# BACKPMAN20_PwrSw.net
KiCad netlist of a schematic drawn in Altium Designer
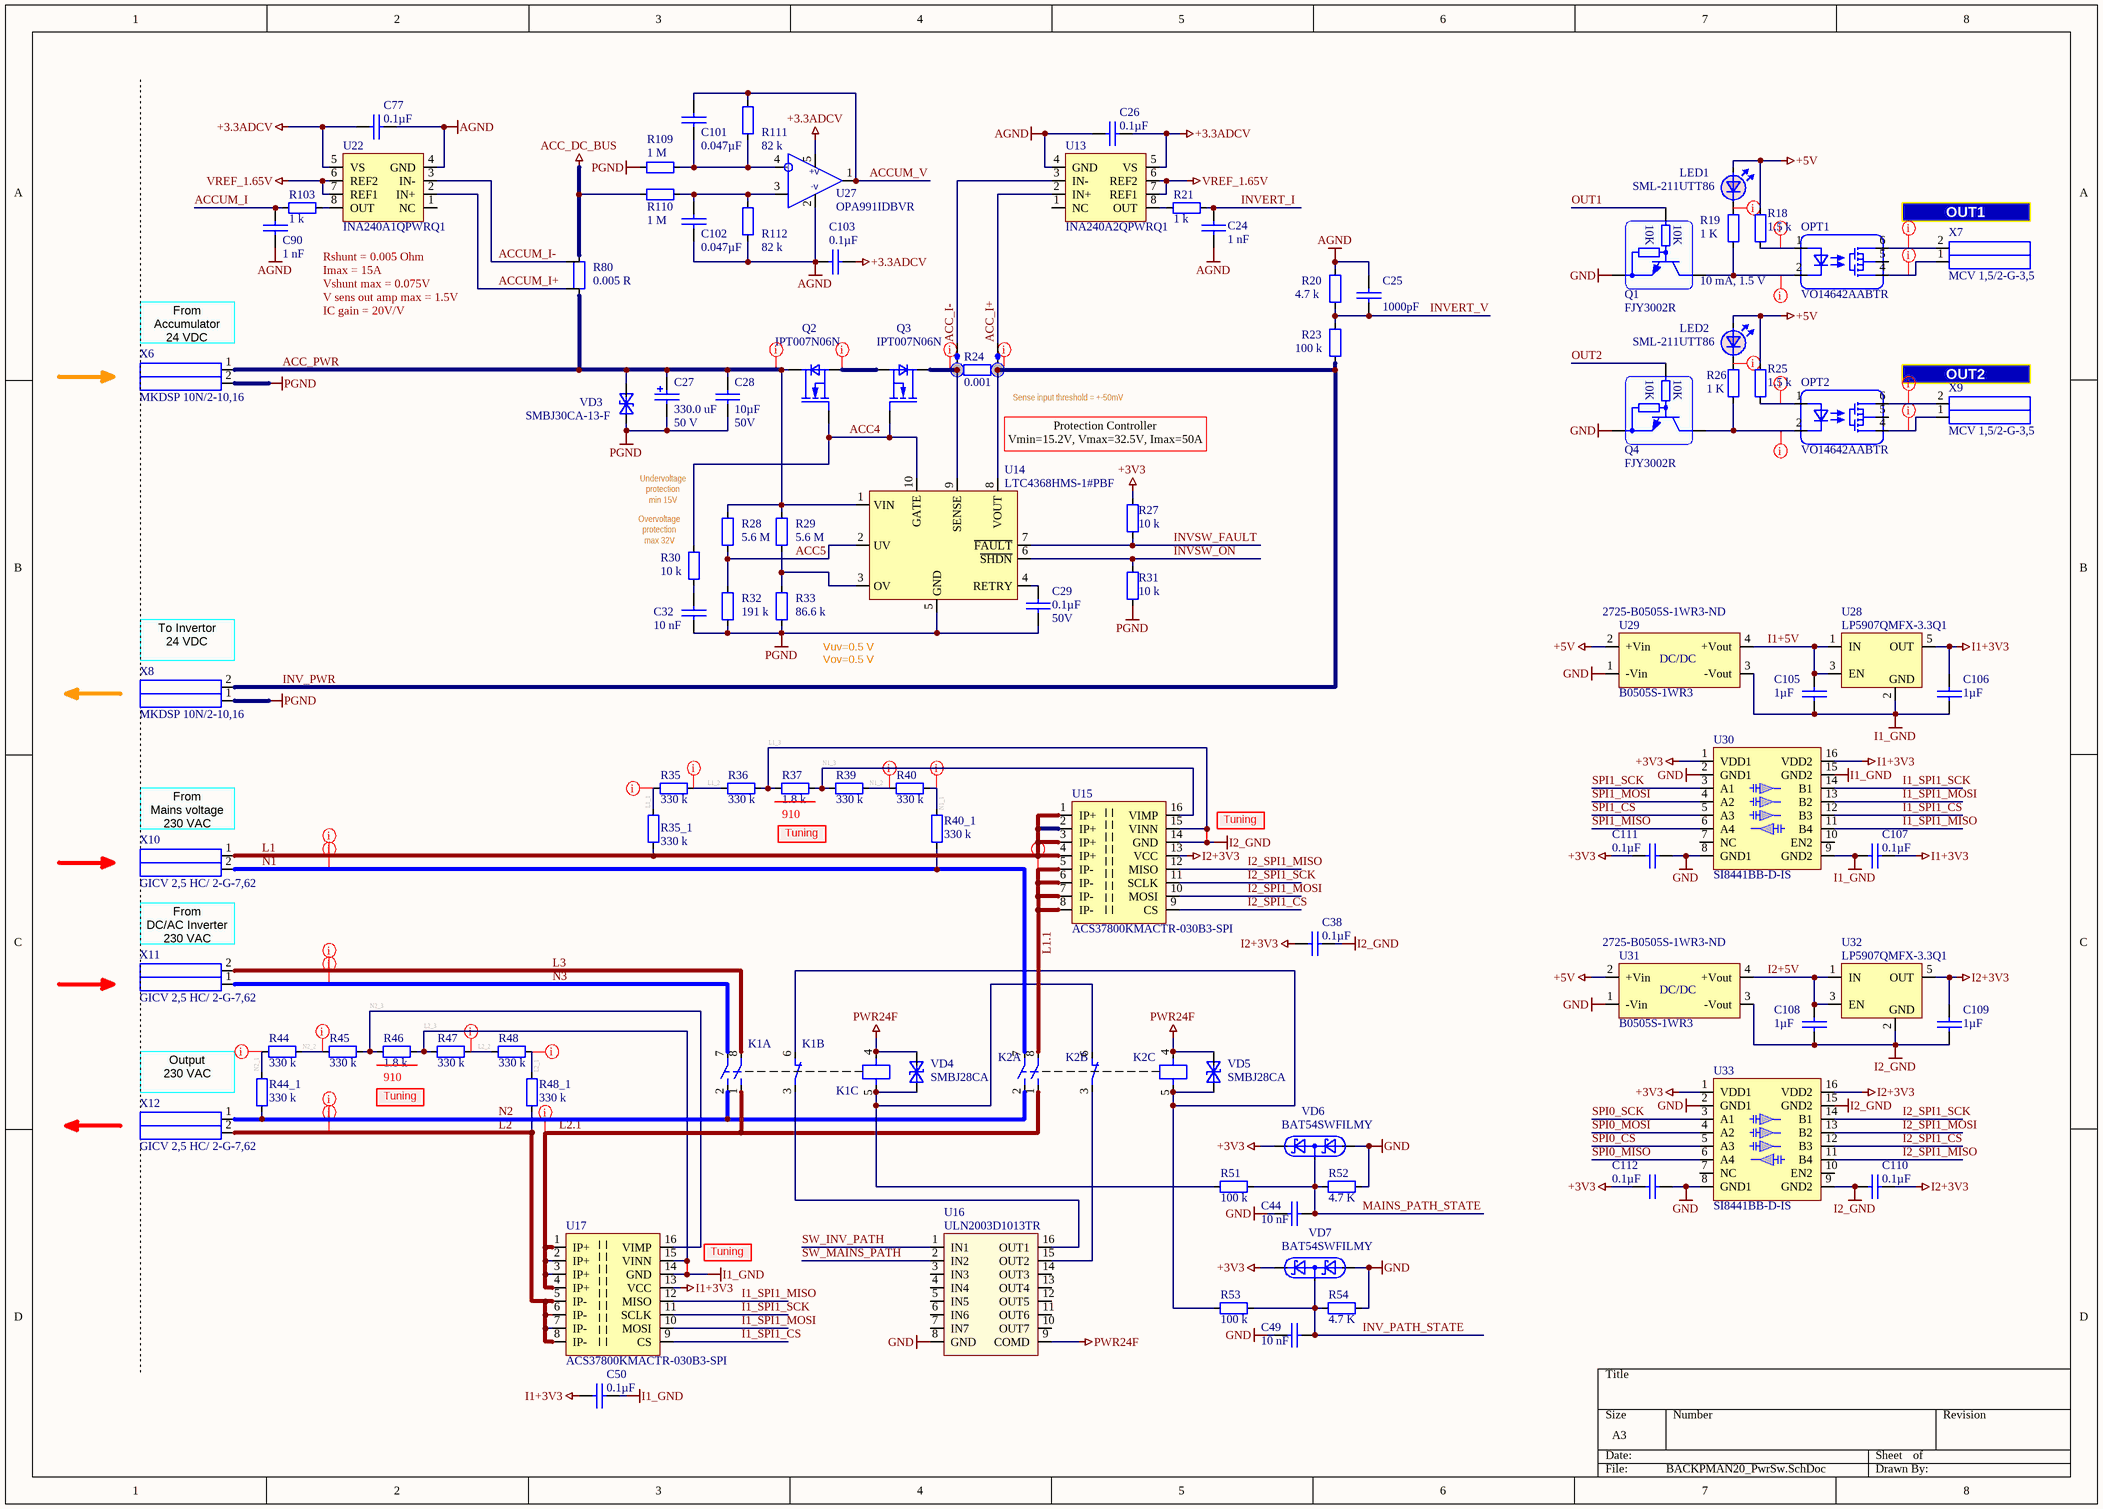
[diagram p0: BACKPMAN20_PwrSw.SchDoc]

(export (version "E")
  (design (tool "Eeschema 10.0.6"))
  (components
    (comp (ref "B1")
      (value "Net tie 0.3mm")
      (footprint "Net tee 0.3 mm")
      (libsource (lib "ea_Mechanical") (part "Net tie 0.3mm"))
    )
    (comp (ref "B2")
      (value "Net tie 0.3mm")
      (footprint "Net tee 0.3 mm")
      (libsource (lib "ea_Mechanical") (part "Net tie 0.3mm"))
    )
    (comp (ref "C24")
      (value "1 nF")
      (footprint "0603 CAP")
      (description "1000pF, ±5%, 50V, X7R, 0603 (1608 Metric), -55°C ~ 125°C, -, General Purpose")
      (fields (field (name "PART NUMBER") "CC0603JRX7R9BB102") (field (name "MANUFACTURER") "Yageo"))
      (libsource (lib "ea_PassivComps") (part "Capacitor"))
    )
    (comp (ref "C25")
      (value "1000pF")
      (footprint "0603 CAP")
      (description "1000pF, ±10%, 16V, X7R, 0603 (1608 Metric), -55°C ~ 125°C, -, General Purpose")
      (fields
        (field (name "PART NUMBER") "885012206034")
        (field (name "MANUFACTURER") "Wurth Electronics Inc.")
      )
      (libsource (lib "ea_PassivComps") (part "Capacitor"))
    )
    (comp (ref "C26")
      (value "0.1µF")
      (footprint "0603 CAP")
      (description "0.1µF, ±10%, 50V, X8L, 0603 (1608 Metric), -55°C ~ 150°C, -, Automotive")
      (fields
        (field (name "PART NUMBER") "GCM188L81H104KA57D")
        (field (name "MANUFACTURER") "Murata Electronics North America")
      )
      (libsource (lib "ea_PassivComps") (part "Capacitor"))
    )
    (comp (ref "C27")
      (value "330.0 uF")
      (footprint "UUD1V331MNL1GS")
      (description "330 uF, 50V, 120 mOhm @ 100kHz, 585 mA, 10x10, -50...+105 C")
      (fields
        (field (name "MANUFACTURER") "Panasonic Electronic Components")
        (field (name "VOLTAGE") "50 V")
        (field (name "TOLERANCE") "±20%")
      )
      (libsource (lib "ea_Capacitors") (part "EEE-FT1H331GP"))
    )
    (comp (ref "C28")
      (value "10µF")
      (footprint "1210 CAP")
      (description "10µF, ±10%, 50V, X7S, 1210 (3225 Metric), -55°C ~ 125°C, Low ESL, General Purpose")
      (fields
        (field (name "VOLTAGE - RATED") "50V")
        (field (name "PART NUMBER") "C3225X7S1H106K250AB")
        (field (name "MANUFACTURER") "TDK Corporation")
      )
      (libsource (lib "ea_PassivComps") (part "Capacitor"))
    )
    (comp (ref "C29")
      (value "0.1µF")
      (footprint "0603 CAP")
      (description "0.1µF, ±10%, 50V, X8L, 0603 (1608 Metric), -55°C ~ 150°C, -, Automotive")
      (fields
        (field (name "VOLTAGE - RATED") "50V")
        (field (name "PART NUMBER") "GCM188L81H104KA57D")
        (field (name "MANUFACTURER") "Murata Electronics North America")
      )
      (libsource (lib "ea_PassivComps") (part "Capacitor"))
    )
    (comp (ref "C32")
      (value "10 nF")
      (footprint "1608[0603]")
      (description "10 nF, 50V, 10%, X7R, 0603 SMD MLC Capacitor")
      (fields (field (name "TOLERANCE") "±10%") (field (name "MANUFACTURER") "Murata Electronics"))
      (libsource (lib "ea_Capacitors") (part "CVNF010K0603"))
    )
    (comp (ref "C38")
      (value "0.1µF")
      (footprint "0603 CAP")
      (description "0.1µF, ±10%, 16V, X7R, 0603 (1608 Metric), -55°C ~ 125°C, -, General Purpose")
      (fields
        (field (name "PART NUMBER") "CL10B104KO8NNNC")
        (field (name "MANUFACTURER") "Samsung Electro-Mechanics")
      )
      (libsource (lib "ea_PassivComps") (part "Capacitor"))
    )
    (comp (ref "C44")
      (value "10 nF")
      (footprint "1608[0603]")
      (description "10 nF, 50V, 10%, X7R, 0603 SMD MLC Capacitor")
      (fields (field (name "TOLERANCE") "±10%") (field (name "MANUFACTURER") "Murata Electronics"))
      (libsource (lib "ea_Capacitors") (part "CVNF010K0603"))
    )
    (comp (ref "C49")
      (value "10 nF")
      (footprint "1608[0603]")
      (description "10 nF, 50V, 10%, X7R, 0603 SMD MLC Capacitor")
      (fields (field (name "TOLERANCE") "±10%") (field (name "MANUFACTURER") "Murata Electronics"))
      (libsource (lib "ea_Capacitors") (part "CVNF010K0603"))
    )
    (comp (ref "C50")
      (value "0.1µF")
      (footprint "0603 CAP")
      (description "0.1µF, ±10%, 16V, X7R, 0603 (1608 Metric), -55°C ~ 125°C, -, General Purpose")
      (fields
        (field (name "PART NUMBER") "CL10B104KO8NNNC")
        (field (name "MANUFACTURER") "Samsung Electro-Mechanics")
      )
      (libsource (lib "ea_PassivComps") (part "Capacitor"))
    )
    (comp (ref "C77")
      (value "0.1µF")
      (footprint "0603 CAP")
      (description "0.1µF, ±10%, 50V, X8L, 0603 (1608 Metric), -55°C ~ 150°C, -, Automotive")
      (fields
        (field (name "PART NUMBER") "GCM188L81H104KA57D")
        (field (name "MANUFACTURER") "Murata Electronics North America")
      )
      (libsource (lib "ea_PassivComps") (part "Capacitor"))
    )
    (comp (ref "C90")
      (value "1 nF")
      (footprint "0603 CAP")
      (description "1000pF, ±5%, 50V, X7R, 0603 (1608 Metric), -55°C ~ 125°C, -, General Purpose")
      (fields (field (name "PART NUMBER") "CC0603JRX7R9BB102") (field (name "MANUFACTURER") "Yageo"))
      (libsource (lib "ea_PassivComps") (part "Capacitor"))
    )
    (comp (ref "C101")
      (value "0.047µF")
      (footprint "0603 CAP")
      (description "0.047µF, ±5%, 50V, X7R, 0603 (1608 Metric), -55°C ~ 125°C, -, General Purpose")
      (fields (field (name "PART NUMBER") "CC0603JRX7R9BB473") (field (name "MANUFACTURER") "Yageo"))
      (libsource (lib "ea_PassivComps") (part "Capacitor"))
    )
    (comp (ref "C102")
      (value "0.047µF")
      (footprint "0603 CAP")
      (description "0.047µF, ±5%, 50V, X7R, 0603 (1608 Metric), -55°C ~ 125°C, -, General Purpose")
      (fields (field (name "PART NUMBER") "CC0603JRX7R9BB473") (field (name "MANUFACTURER") "Yageo"))
      (libsource (lib "ea_PassivComps") (part "Capacitor"))
    )
    (comp (ref "C103")
      (value "0.1µF")
      (footprint "0603 CAP")
      (description "0.1µF, ±10%, 50V, X8L, 0603 (1608 Metric), -55°C ~ 150°C, -, Automotive")
      (fields
        (field (name "PART NUMBER") "GCM188L81H104KA57D")
        (field (name "MANUFACTURER") "Murata Electronics North America")
      )
      (libsource (lib "ea_PassivComps") (part "Capacitor"))
    )
    (comp (ref "C105")
      (value "1µF")
      (footprint "0603 CAP")
      (description "1µF, ±10%, 16V, X7R, 0603 (1608 Metric), -55°C ~ 125°C, -, General Purpose")
      (fields
        (field (name "PART NUMBER") "CL10B105KO8NNNC")
        (field (name "MANUFACTURER") "Samsung Electro-Mechanics")
      )
      (libsource (lib "ea_PassivComps") (part "Capacitor"))
    )
    (comp (ref "C106")
      (value "1µF")
      (footprint "0603 CAP")
      (description "1µF, ±10%, 16V, X7R, 0603 (1608 Metric), -55°C ~ 125°C, -, General Purpose")
      (fields
        (field (name "PART NUMBER") "CL10B105KO8NNNC")
        (field (name "MANUFACTURER") "Samsung Electro-Mechanics")
      )
      (libsource (lib "ea_PassivComps") (part "Capacitor"))
    )
    (comp (ref "C107")
      (value "0.1µF")
      (footprint "0603 CAP")
      (description "0.1µF, ±10%, 16V, X7R, 0603 (1608 Metric), -55°C ~ 125°C, -, General Purpose")
      (fields
        (field (name "PART NUMBER") "CL10B104KO8NNNC")
        (field (name "MANUFACTURER") "Samsung Electro-Mechanics")
      )
      (libsource (lib "ea_PassivComps") (part "Capacitor"))
    )
    (comp (ref "C108")
      (value "1µF")
      (footprint "0603 CAP")
      (description "1µF, ±10%, 16V, X7R, 0603 (1608 Metric), -55°C ~ 125°C, -, General Purpose")
      (fields
        (field (name "PART NUMBER") "CL10B105KO8NNNC")
        (field (name "MANUFACTURER") "Samsung Electro-Mechanics")
      )
      (libsource (lib "ea_PassivComps") (part "Capacitor"))
    )
    (comp (ref "C109")
      (value "1µF")
      (footprint "0603 CAP")
      (description "1µF, ±10%, 16V, X7R, 0603 (1608 Metric), -55°C ~ 125°C, -, General Purpose")
      (fields
        (field (name "PART NUMBER") "CL10B105KO8NNNC")
        (field (name "MANUFACTURER") "Samsung Electro-Mechanics")
      )
      (libsource (lib "ea_PassivComps") (part "Capacitor"))
    )
    (comp (ref "C110")
      (value "0.1µF")
      (footprint "0603 CAP")
      (description "0.1µF, ±10%, 16V, X7R, 0603 (1608 Metric), -55°C ~ 125°C, -, General Purpose")
      (fields
        (field (name "PART NUMBER") "CL10B104KO8NNNC")
        (field (name "MANUFACTURER") "Samsung Electro-Mechanics")
      )
      (libsource (lib "ea_PassivComps") (part "Capacitor"))
    )
    (comp (ref "C111")
      (value "0.1µF")
      (footprint "0603 CAP")
      (description "0.1µF, ±10%, 16V, X7R, 0603 (1608 Metric), -55°C ~ 125°C, -, General Purpose")
      (fields
        (field (name "PART NUMBER") "CL10B104KO8NNNC")
        (field (name "MANUFACTURER") "Samsung Electro-Mechanics")
      )
      (libsource (lib "ea_PassivComps") (part "Capacitor"))
    )
    (comp (ref "C112")
      (value "0.1µF")
      (footprint "0603 CAP")
      (description "0.1µF, ±10%, 16V, X7R, 0603 (1608 Metric), -55°C ~ 125°C, -, General Purpose")
      (fields
        (field (name "PART NUMBER") "CL10B104KO8NNNC")
        (field (name "MANUFACTURER") "Samsung Electro-Mechanics")
      )
      (libsource (lib "ea_PassivComps") (part "Capacitor"))
    )
    (comp (ref "K1")
      (value "AHES4292")
      (footprint "AHES4292")
      (fields (field (name "PARTNUM") "255-5914-ND") (field (name "MANUFACTURER") "Panasonic Electric Works"))
      (libsource (lib "ea_Relay") (part "AHES4292"))
    )
    (comp (ref "K2")
      (value "AHES4292")
      (footprint "AHES4292")
      (fields (field (name "PARTNUM") "255-5914-ND") (field (name "MANUFACTURER") "Panasonic Electric Works"))
      (libsource (lib "ea_Relay") (part "AHES4292"))
    )
    (comp (ref "LED1")
      (value "SML-211UTT86")
      (footprint "0805 LED")
      (description "0805 red LED, hibright, 2 mA, 1.8V, 130°")
      (fields (field (name "MANUFACTURER") "Rohm") (field (name "PARTNUM") "511-1292-1-ND"))
      (libsource (lib "ea_Indicators") (part "SML-211UTT86"))
    )
    (comp (ref "LED2")
      (value "SML-211UTT86")
      (footprint "0805 LED")
      (description "0805 red LED, hibright, 2 mA, 1.8V, 130°")
      (fields (field (name "MANUFACTURER") "Rohm") (field (name "PARTNUM") "511-1292-1-ND"))
      (libsource (lib "ea_Indicators") (part "SML-211UTT86"))
    )
    (comp (ref "OPT1")
      (value "VO14642AABTR")
      (footprint "DIP-6 SMD")
      (description "Opto relay, SPST-NO, AC DC, 250 mOhm, 2A, 0-60V, 6-SMD, -55..50C")
      (fields
        (field (name "MANUFACTURER") "Vishay Semiconductor Opto Division")
        (field (name "PARTNUM") "VO14642AABCT-ND")
      )
      (libsource (lib "ea_Opto") (part "VO14642AABTR"))
    )
    (comp (ref "OPT2")
      (value "VO14642AABTR")
      (footprint "DIP-6 SMD")
      (description "Opto relay, SPST-NO, AC DC, 250 mOhm, 2A, 0-60V, 6-SMD, -55..50C")
      (fields
        (field (name "MANUFACTURER") "Vishay Semiconductor Opto Division")
        (field (name "PARTNUM") "VO14642AABCT-ND")
      )
      (libsource (lib "ea_Opto") (part "VO14642AABTR"))
    )
    (comp (ref "Q1")
      (value "FJY3002R")
      (footprint "SOT-523F")
      (description "NPN 50V 100MA SOT-523F")
      (fields
        (field (name "MANUFACTURER") "Fairchild Semiconductor")
        (field (name "PARTNUM") "FJY3002RCT-ND")
      )
      (libsource (lib "ea_Transistors") (part "FJY3002R"))
    )
    (comp (ref "Q2")
      (value "IPT007N06N")
      (footprint "PG-HSOF-8-1 (8-PowerSFN) Infineon")
      (description "MOSFET N CH 60V 300A, 0.75 mOhm @ 150A 10V, 287nC @ 10V, PG-HSOF-8-1, -55°C ~ 175°C")
      (fields
        (field (name "MANUFACTURER") "Infineon Technologies")
        (field (name "PARTNUM") "IPT007N06NATMA1CT-ND")
      )
      (libsource (lib "ea_MOSFET_&_drivers") (part "IPT007N06NATMA1"))
    )
    (comp (ref "Q3")
      (value "IPT007N06N")
      (footprint "PG-HSOF-8-1 (8-PowerSFN) Infineon")
      (description "MOSFET N CH 60V 300A, 0.75 mOhm @ 150A 10V, 287nC @ 10V, PG-HSOF-8-1, -55°C ~ 175°C")
      (fields
        (field (name "MANUFACTURER") "Infineon Technologies")
        (field (name "PARTNUM") "IPT007N06NATMA1CT-ND")
      )
      (libsource (lib "ea_MOSFET_&_drivers") (part "IPT007N06NATMA1"))
    )
    (comp (ref "Q4")
      (value "FJY3002R")
      (footprint "SOT-523F")
      (description "NPN 50V 100MA SOT-523F")
      (fields
        (field (name "MANUFACTURER") "Fairchild Semiconductor")
        (field (name "PARTNUM") "FJY3002RCT-ND")
      )
      (libsource (lib "ea_Transistors") (part "FJY3002R"))
    )
    (comp (ref "R18")
      (value "1.5 k")
      (footprint "0603")
      (fields
        (field (name "MANUFACTURER") "Stackpole Electronics Inc.")
        (field (name "TOLERANCE") "±1%")
        (field (name "VOLTAGE") "75V")
      )
      (libsource (lib "") (part "Resistor_2"))
    )
    (comp (ref "R19")
      (value "1 K")
      (footprint "0603")
      (description "1 K, 1%, 0603, SMD Resistor, Taped")
      (fields (field (name "MANUFACTURER") "Vishay") (field (name "TOLERANCE") "1%"))
      (libsource (lib "ea_Resistors_0603") (part "RL0603K001-1"))
    )
    (comp (ref "R20")
      (value "4.7 k")
      (footprint "0603")
      (fields
        (field (name "MANUFACTURER") "Stackpole Electronics Inc.")
        (field (name "TOLERANCE") "±1%")
        (field (name "VOLTAGE") "75V")
      )
      (libsource (lib "") (part "Resistor_2"))
    )
    (comp (ref "R21")
      (value "1 k")
      (footprint "0603")
      (fields
        (field (name "MANUFACTURER") "Stackpole Electronics Inc.")
        (field (name "TOLERANCE") "±1%")
        (field (name "VOLTAGE") "75V")
      )
      (libsource (lib "") (part "Resistor_1"))
    )
    (comp (ref "R23")
      (value "100 k")
      (footprint "1206")
      (fields
        (field (name "MANUFACTURER") "Stackpole Electronics Inc.")
        (field (name "TOLERANCE") "±1%")
        (field (name "VOLTAGE") "200V")
      )
      (libsource (lib "") (part "Resistor_2"))
    )
    (comp (ref "R24")
      (value "0.001")
      (footprint "WSR52L000FEA")
      (description "Curr.sens.res. 0.001 OHM 5W 1% 4527 SMD")
      (fields (field (name "MANUFACTURER") "Vishay/Dale") (field (name "TOLERANCE") "1%"))
      (libsource (lib "ea_Resistors") (part "WSR51L000FEA"))
    )
    (comp (ref "R25")
      (value "1.5 k")
      (footprint "0603")
      (fields
        (field (name "MANUFACTURER") "Stackpole Electronics Inc.")
        (field (name "TOLERANCE") "±1%")
        (field (name "VOLTAGE") "75V")
      )
      (libsource (lib "") (part "Resistor_2"))
    )
    (comp (ref "R26")
      (value "1 K")
      (footprint "0603")
      (description "1 K, 1%, 0603, SMD Resistor, Taped")
      (fields (field (name "MANUFACTURER") "Vishay") (field (name "TOLERANCE") "1%"))
      (libsource (lib "ea_Resistors_0603") (part "RL0603K001-1"))
    )
    (comp (ref "R27")
      (value "10 k")
      (footprint "0603")
      (fields
        (field (name "MANUFACTURER") "Bourns Inc.")
        (field (name "TOLERANCE") "±1%")
        (field (name "VOLTAGE") "75V")
      )
      (libsource (lib "ea_PassivComps") (part "Resistor"))
    )
    (comp (ref "R28")
      (value "5.6 M")
      (footprint "0805")
      (fields
        (field (name "MANUFACTURER") "Vishay Dale")
        (field (name "TOLERANCE") "±1%")
        (field (name "VOLTAGE") "150V")
      )
      (libsource (lib "ea_PassivComps") (part "Resistor"))
    )
    (comp (ref "R29")
      (value "5.6 M")
      (footprint "0805")
      (fields
        (field (name "MANUFACTURER") "Vishay Dale")
        (field (name "TOLERANCE") "±1%")
        (field (name "VOLTAGE") "150V")
      )
      (libsource (lib "ea_PassivComps") (part "Resistor"))
    )
    (comp (ref "R30")
      (value "10 k")
      (footprint "0603")
      (fields
        (field (name "MANUFACTURER") "Bourns Inc.")
        (field (name "TOLERANCE") "±1%")
        (field (name "VOLTAGE") "75V")
      )
      (libsource (lib "") (part "Resistor_3"))
    )
    (comp (ref "R31")
      (value "10 k")
      (footprint "0603")
      (fields
        (field (name "MANUFACTURER") "Bourns Inc.")
        (field (name "TOLERANCE") "±1%")
        (field (name "VOLTAGE") "75V")
      )
      (libsource (lib "ea_PassivComps") (part "Resistor"))
    )
    (comp (ref "R32")
      (value "191 k")
      (footprint "0603")
      (fields
        (field (name "MANUFACTURER") "Stackpole Electronics Inc.")
        (field (name "TOLERANCE") "±1%")
        (field (name "VOLTAGE") "75V")
      )
      (libsource (lib "ea_PassivComps") (part "Resistor"))
    )
    (comp (ref "R33")
      (value "86.6 k")
      (footprint "0603")
      (fields
        (field (name "MANUFACTURER") "Stackpole Electronics Inc.")
        (field (name "TOLERANCE") "±1%")
        (field (name "VOLTAGE") "75V")
      )
      (libsource (lib "ea_PassivComps") (part "Resistor"))
    )
    (comp (ref "R35")
      (value "330 k")
      (footprint "1206")
      (fields
        (field (name "MANUFACTURER") "Stackpole Electronics Inc.")
        (field (name "TOLERANCE") "±1%")
        (field (name "VOLTAGE") "200V")
      )
      (libsource (lib "") (part "Resistor_1"))
    )
    (comp (ref "R35_1")
      (value "330 k")
      (footprint "1206")
      (fields
        (field (name "MANUFACTURER") "Stackpole Electronics Inc.")
        (field (name "TOLERANCE") "±1%")
        (field (name "VOLTAGE") "200V")
      )
      (libsource (lib "ea_PassivComps") (part "Resistor"))
    )
    (comp (ref "R36")
      (value "330 k")
      (footprint "1206")
      (fields
        (field (name "MANUFACTURER") "Stackpole Electronics Inc.")
        (field (name "TOLERANCE") "±1%")
        (field (name "VOLTAGE") "200V")
      )
      (libsource (lib "") (part "Resistor_1"))
    )
    (comp (ref "R37")
      (value "1.8 k")
      (footprint "0603")
      (fields
        (field (name "MANUFACTURER") "Stackpole Electronics Inc.")
        (field (name "TOLERANCE") "±1%")
        (field (name "VOLTAGE") "75V")
      )
      (libsource (lib "") (part "Resistor_2"))
    )
    (comp (ref "R39")
      (value "330 k")
      (footprint "1206")
      (fields
        (field (name "MANUFACTURER") "Stackpole Electronics Inc.")
        (field (name "TOLERANCE") "±1%")
        (field (name "VOLTAGE") "200V")
      )
      (libsource (lib "") (part "Resistor_1"))
    )
    (comp (ref "R40")
      (value "330 k")
      (footprint "1206")
      (fields
        (field (name "MANUFACTURER") "Stackpole Electronics Inc.")
        (field (name "TOLERANCE") "±1%")
        (field (name "VOLTAGE") "200V")
      )
      (libsource (lib "") (part "Resistor_1"))
    )
    (comp (ref "R40_1")
      (value "330 k")
      (footprint "1206")
      (fields
        (field (name "MANUFACTURER") "Stackpole Electronics Inc.")
        (field (name "TOLERANCE") "±1%")
        (field (name "VOLTAGE") "200V")
      )
      (libsource (lib "ea_PassivComps") (part "Resistor"))
    )
    (comp (ref "R44")
      (value "330 k")
      (footprint "1206")
      (fields
        (field (name "MANUFACTURER") "Stackpole Electronics Inc.")
        (field (name "TOLERANCE") "±1%")
        (field (name "VOLTAGE") "200V")
      )
      (libsource (lib "") (part "Resistor_1"))
    )
    (comp (ref "R44_1")
      (value "330 k")
      (footprint "1206")
      (fields
        (field (name "MANUFACTURER") "Stackpole Electronics Inc.")
        (field (name "TOLERANCE") "±1%")
        (field (name "VOLTAGE") "200V")
      )
      (libsource (lib "ea_PassivComps") (part "Resistor"))
    )
    (comp (ref "R45")
      (value "330 k")
      (footprint "1206")
      (fields
        (field (name "MANUFACTURER") "Stackpole Electronics Inc.")
        (field (name "TOLERANCE") "±1%")
        (field (name "VOLTAGE") "200V")
      )
      (libsource (lib "") (part "Resistor_1"))
    )
    (comp (ref "R46")
      (value "1.8 k")
      (footprint "0603")
      (fields
        (field (name "MANUFACTURER") "Stackpole Electronics Inc.")
        (field (name "TOLERANCE") "±1%")
        (field (name "VOLTAGE") "75V")
      )
      (libsource (lib "") (part "Resistor_2"))
    )
    (comp (ref "R47")
      (value "330 k")
      (footprint "1206")
      (fields
        (field (name "MANUFACTURER") "Stackpole Electronics Inc.")
        (field (name "TOLERANCE") "±1%")
        (field (name "VOLTAGE") "200V")
      )
      (libsource (lib "") (part "Resistor_1"))
    )
    (comp (ref "R48")
      (value "330 k")
      (footprint "1206")
      (fields
        (field (name "MANUFACTURER") "Stackpole Electronics Inc.")
        (field (name "TOLERANCE") "±1%")
        (field (name "VOLTAGE") "200V")
      )
      (libsource (lib "") (part "Resistor_1"))
    )
    (comp (ref "R48_1")
      (value "330 k")
      (footprint "1206")
      (fields
        (field (name "MANUFACTURER") "Stackpole Electronics Inc.")
        (field (name "TOLERANCE") "±1%")
        (field (name "VOLTAGE") "200V")
      )
      (libsource (lib "ea_PassivComps") (part "Resistor"))
    )
    (comp (ref "R51")
      (value "100 k")
      (footprint "1206")
      (fields
        (field (name "MANUFACTURER") "Stackpole Electronics Inc.")
        (field (name "TOLERANCE") "±1%")
        (field (name "VOLTAGE") "200V")
      )
      (libsource (lib "") (part "Resistor_1"))
    )
    (comp (ref "R52")
      (value "4.7 K")
      (footprint "0603")
      (description "4.7 K, 1%, 0603, SMD Resistor, Taped")
      (fields (field (name "MANUFACTURER") "Vishay Dale") (field (name "TOLERANCE") "1%"))
      (libsource (lib "ea_Resistors") (part "RL0603K004.7-1"))
    )
    (comp (ref "R53")
      (value "100 k")
      (footprint "1206")
      (fields
        (field (name "MANUFACTURER") "Stackpole Electronics Inc.")
        (field (name "TOLERANCE") "±1%")
        (field (name "VOLTAGE") "200V")
      )
      (libsource (lib "") (part "Resistor_1"))
    )
    (comp (ref "R54")
      (value "4.7 K")
      (footprint "0603")
      (description "4.7 K, 1%, 0603, SMD Resistor, Taped")
      (fields (field (name "MANUFACTURER") "Vishay Dale") (field (name "TOLERANCE") "1%"))
      (libsource (lib "ea_Resistors") (part "RL0603K004.7-1"))
    )
    (comp (ref "R80")
      (value "0.005 R")
      (footprint "FC4L110")
      (description "Curr.sens.res. 0.005 OHM 5W 1% , 4320 (50110 Metric)")
      (fields (field (name "MANUFACTURER") "Ohmite") (field (name "TOLERANCE") "1%"))
      (libsource (lib "ea_Resistors") (part "FC4L110R005FER"))
    )
    (comp (ref "R103")
      (value "1 k")
      (footprint "0603")
      (fields
        (field (name "MANUFACTURER") "Stackpole Electronics Inc.")
        (field (name "TOLERANCE") "±1%")
        (field (name "VOLTAGE") "75V")
      )
      (libsource (lib "") (part "Resistor_3"))
    )
    (comp (ref "R109")
      (value "1 M")
      (footprint "0603")
      (description "1 MOhms, ±0.1%, 0.1W, 1/10W, Thin Film, ±25ppm/°C, 0603 (1608 Metric), -55°C ~ 155°C, -")
      (fields (field (name "MANUFACTURER") "Yageo") (field (name "TOLERANCE") "±0.1%"))
      (libsource (lib "") (part "Resistor_1"))
    )
    (comp (ref "R110")
      (value "1 M")
      (footprint "0603")
      (description "1 MOhms, ±0.1%, 0.1W, 1/10W, Thin Film, ±25ppm/°C, 0603 (1608 Metric), -55°C ~ 155°C, -")
      (fields (field (name "MANUFACTURER") "Yageo") (field (name "TOLERANCE") "±0.1%"))
      (libsource (lib "") (part "Resistor_1"))
    )
    (comp (ref "R111")
      (value "82 k")
      (footprint "0603")
      (fields
        (field (name "MANUFACTURER") "Panasonic Electronic Components")
        (field (name "TOLERANCE") "±0.1%")
        (field (name "VOLTAGE") "75V")
      )
      (libsource (lib "ea_PassivComps") (part "Resistor"))
    )
    (comp (ref "R112")
      (value "82 k")
      (footprint "0603")
      (fields
        (field (name "MANUFACTURER") "Panasonic Electronic Components")
        (field (name "TOLERANCE") "±0.1%")
        (field (name "VOLTAGE") "75V")
      )
      (libsource (lib "ea_PassivComps") (part "Resistor"))
    )
    (comp (ref "U13")
      (value "INA240A2QPWRQ1")
      (footprint "TI TSSOP-8")
      (description "Current Sense Amplifier, 50V/V, 2V/us, 400KHz, -40°C ~ 125°C, 8-TSSOP")
      (fields (field (name "MANUFACTURER") "Texas Instruments") (field (name "PARTNUM") "296-50473-1-ND"))
      (libsource (lib "ea_IC_OPAmps_AnComparators") (part "INA240A2QPWRQ1"))
    )
    (comp (ref "U14")
      (value "LTC4368HMS-1#PBF")
      (footprint "10-Lead Plastic MSOP Linear")
      (fields (field (name "MANUFACTURER") "Analog Devices") (field (name "PARTNUM") "LTC4368HMS-1#PBF-ND"))
      (libsource (lib "ea_IC_drivers") (part "LTC4368HMS-1_PBF"))
    )
    (comp (ref "U15")
      (value "ACS37800KMACTR-030B3-SPI")
      (footprint "16-Pin SOICW")
      (fields
        (field (name "MANUFACTURER") "Allegro MicroSystems")
        (field (name "PARTNUM") "620-ACS37800KMACTR-030B3-SPICT-ND")
      )
      (libsource (lib "ea_IC_sensors") (part "ACS37800KMACTR-030B3-SPI"))
    )
    (comp (ref "U16")
      (value "ULN2003D1013TR")
      (footprint "SO-16")
      (description "TRANS 7 NPN DARL 50V 500MA 16SO")
      (fields (field (name "MANUFACTURER") "STMicroelectronics") (field (name "PARTNUM") "497-2345-1-ND"))
      (libsource (lib "ea_IC_registers_buffers") (part "ULN2003D1013TR"))
    )
    (comp (ref "U17")
      (value "ACS37800KMACTR-030B3-SPI")
      (footprint "16-Pin SOICW")
      (fields
        (field (name "MANUFACTURER") "Allegro MicroSystems")
        (field (name "PARTNUM") "620-ACS37800KMACTR-030B3-SPICT-ND")
      )
      (libsource (lib "ea_IC_sensors") (part "ACS37800KMACTR-030B3-SPI"))
    )
    (comp (ref "U22")
      (value "INA240A1QPWRQ1")
      (footprint "TI TSSOP-8")
      (description "Current Sense Amplifier, 20V/V, 2V/us, 400KHz, -40°C ~ 125°C, 8-TSSOP")
      (fields (field (name "MANUFACTURER") "Texas Instruments") (field (name "PARTNUM") "296-50472-1-ND"))
      (libsource (lib "ea_IC_OPAmps_AnComparators") (part "INA240A1QPWRQ1"))
    )
    (comp (ref "U27")
      (value "OPA991IDBVR")
      (footprint "SOT23-5")
      (description "OpAmp,  Rail-to-Rail,  4,5MHz, VSS 2.7V ~ 40V, Vofs125µV,  SOT-23-5, -40°C ~ 125°C")
      (fields
        (field (name "MANUFACTURER") "Texas Instruments")
        (field (name "PARTNUM") "296-OPA991IDBVRCT-ND")
      )
      (libsource (lib "ea_IC_OPAmps_AnComparators") (part "OPA991IDBVR"))
    )
    (comp (ref "U28")
      (value "LP5907QMFX-3.3Q1")
      (footprint "SOT23-5")
      (description "LDO 3.3 V, 250 mA, Vin < 5.5V, Iq < 12uA, -40..+125 C, SOT23-5")
      (fields (field (name "MANUFACTURER") "Texas Instruments") (field (name "PARTNUM") "296-40365-1-ND"))
      (libsource (lib "ea_IC_Power_Reg_Ref_Sw") (part "LP5907QMFX-3.3Q1"))
    )
    (comp (ref "U29")
      (value "B0505S-1WR3")
      (footprint "Recom 4-SIP module")
      (description "200mA, DC-DC Unregulated Single Output , 5V in, 5 V out,  -40°C ~ 105°C")
      (fields
        (field (name "MANUFACTURER") "Mornsun America, LLC")
        (field (name "PARTNUM") "2725-B0505S-1WR3-ND")
        (field (name "SUPPLIER PART NUMBER 1") "2725-B0505S-1WR3-ND")
      )
      (libsource (lib "ea_PowerSources") (part "B0505S-1WR3"))
    )
    (comp (ref "U30")
      (value "SI8441BB-D-IS")
      (footprint "SO-G16/D10.4")
      (description "IC ISOLATOR 4CH 5.5V 16-SOIC")
      (fields
        (field (name "MANUFACTURER") "Silicon Laboratories Inc")
        (field (name "PARTNUM") "336-1762-5-ND")
      )
      (libsource (lib "ea_IC_Isolated_Interfaces") (part "SI8441BB-D-IS"))
    )
    (comp (ref "U31")
      (value "B0505S-1WR3")
      (footprint "Recom 4-SIP module")
      (description "200mA, DC-DC Unregulated Single Output , 5V in, 5 V out,  -40°C ~ 105°C")
      (fields
        (field (name "MANUFACTURER") "Mornsun America, LLC")
        (field (name "PARTNUM") "2725-B0505S-1WR3-ND")
        (field (name "SUPPLIER PART NUMBER 1") "2725-B0505S-1WR3-ND")
      )
      (libsource (lib "ea_PowerSources") (part "B0505S-1WR3"))
    )
    (comp (ref "U32")
      (value "LP5907QMFX-3.3Q1")
      (footprint "SOT23-5")
      (description "LDO 3.3 V, 250 mA, Vin < 5.5V, Iq < 12uA, -40..+125 C, SOT23-5")
      (fields (field (name "MANUFACTURER") "Texas Instruments") (field (name "PARTNUM") "296-40365-1-ND"))
      (libsource (lib "ea_IC_Power_Reg_Ref_Sw") (part "LP5907QMFX-3.3Q1"))
    )
    (comp (ref "U33")
      (value "SI8441BB-D-IS")
      (footprint "SO-G16/D10.4")
      (description "IC ISOLATOR 4CH 5.5V 16-SOIC")
      (fields
        (field (name "MANUFACTURER") "Silicon Laboratories Inc")
        (field (name "PARTNUM") "336-1762-5-ND")
      )
      (libsource (lib "ea_IC_Isolated_Interfaces") (part "SI8441BB-D-IS"))
    )
    (comp (ref "VD3")
      (value "SMBJ30CA-13-F")
      (footprint "DO-214AA_SMBJ BI")
      (description "TVS 600W, Vbr=33.3V, Vcl=48.4V,  Bidirectional, SMB, -55°C ~ 150°C")
      (fields
        (field (name "MANUFACTURER") "Diodes Incorporated")
        (field (name "PARTNUM") "SMBJ30CA-FDICT-ND")
      )
      (libsource (lib "ea_TVS_protection") (part "SMBJ30CA-13-F"))
    )
    (comp (ref "VD4")
      (value "SMBJ28CA")
      (footprint "DO-214AA_SMBJ")
      (description "TVS 600W 28V Bidirectional")
      (fields (field (name "MANUFACTURER") "Littelfuse") (field (name "PARTNUM") "SMBJ28CABCT-ND"))
      (libsource (lib "ea_TVS_protection") (part "SMBJ28CA"))
    )
    (comp (ref "VD5")
      (value "SMBJ28CA")
      (footprint "DO-214AA_SMBJ")
      (description "TVS 600W 28V Bidirectional")
      (fields (field (name "MANUFACTURER") "Littelfuse") (field (name "PARTNUM") "SMBJ28CABCT-ND"))
      (libsource (lib "ea_TVS_protection") (part "SMBJ28CA"))
    )
    (comp (ref "VD6")
      (value "BAT54SWFILMY")
      (footprint "SOT323-3")
      (description "Series Shottky Diodes array, 40V, 300 mA, SOT-323, -40°C...150°C")
      (fields (field (name "MANUFACTURER") "STMicroelectronics") (field (name "PARTNUM") "497-17757-1-ND"))
      (libsource (lib "ea_Diodes") (part "BAT54SWFILMY"))
    )
    (comp (ref "VD7")
      (value "BAT54SWFILMY")
      (footprint "SOT323-3")
      (description "Series Shottky Diodes array, 40V, 300 mA, SOT-323, -40°C...150°C")
      (fields (field (name "MANUFACTURER") "STMicroelectronics") (field (name "PARTNUM") "497-17757-1-ND"))
      (libsource (lib "ea_Diodes") (part "BAT54SWFILMY"))
    )
    (comp (ref "X6")
      (value "MKDSP 10N/2-10,16")
      (footprint "MKDSP 10N/ 2-10,16")
      (description "TERMINAL BLOCK, PCB, 10.16MM, 2WAY")
      (fields (field (name "MANUFACTURER") "PHOENIX CONTACT") (field (name "PARTNUM") "1734796"))
      (libsource (lib "ea_PhoenixContacts") (part "MKDSP 10N/2-10,16"))
    )
    (comp (ref "X7")
      (value "MCV 1,5/2-G-3,5")
      (footprint "mcv1.5-2-g_3.5 Green  + MC 1,5 2-ST-3,5 - 1840366")
      (description "HEADER, VERTICAL, 3.5MM, 2WAY")
      (fields (field (name "MANUFACTURER") "PHOENIX CONTACT") (field (name "PARTNUM") "1843606"))
      (libsource (lib "ea_PhoenixContacts") (part "MCV 1,5/2-G-3,5"))
    )
    (comp (ref "X8")
      (value "MKDSP 10N/2-10,16")
      (footprint "MKDSP 10N/ 2-10,16")
      (description "TERMINAL BLOCK, PCB, 10.16MM, 2WAY")
      (fields (field (name "MANUFACTURER") "PHOENIX CONTACT") (field (name "PARTNUM") "1734796"))
      (libsource (lib "ea_PhoenixContacts") (part "MKDSP 10N/2-10,16"))
    )
    (comp (ref "X9")
      (value "MCV 1,5/2-G-3,5")
      (footprint "mcv1.5-2-g_3.5 Green  + MC 1,5 2-ST-3,5 - 1840366")
      (description "HEADER, VERTICAL, 3.5MM, 2WAY")
      (fields (field (name "MANUFACTURER") "PHOENIX CONTACT") (field (name "PARTNUM") "1843606"))
      (libsource (lib "ea_PhoenixContacts") (part "MCV 1,5/2-G-3,5"))
    )
    (comp (ref "X10")
      (value "GICV 2,5 HC/ 2-G-7,62")
      (footprint "1756485 GICV 2,5 HC/2 -G-7,62")
      (fields (field (name "MANUFACTURER") "PHOENIX CONTACT") (field (name "PARTNUM") "1756485"))
      (libsource (lib "ea_Connectors_Power") (part "GICV 2,5 HC/ 2-G-7,62"))
    )
    (comp (ref "X11")
      (value "GICV 2,5 HC/ 2-G-7,62")
      (footprint "1756485 GICV 2,5 HC/2 -G-7,62")
      (fields (field (name "MANUFACTURER") "PHOENIX CONTACT") (field (name "PARTNUM") "1756485"))
      (libsource (lib "ea_Connectors_Power") (part "GICV 2,5 HC/ 2-G-7,62"))
    )
    (comp (ref "X12")
      (value "GICV 2,5 HC/ 2-G-7,62")
      (footprint "1756485 GICV 2,5 HC/2 -G-7,62")
      (fields (field (name "MANUFACTURER") "PHOENIX CONTACT") (field (name "PARTNUM") "1756485"))
      (libsource (lib "ea_Connectors_Power") (part "GICV 2,5 HC/ 2-G-7,62"))
    )
  )
  (nets
    (net (code "1") (name "+3.3ADCV") (class "Default")
      (node (ref "C103") (pin "1") (pinfunction "1_1") (pintype "passive"))
      (node (ref "C26") (pin "1") (pinfunction "1_1") (pintype "passive"))
      (node (ref "C77") (pin "1") (pinfunction "1_1") (pintype "passive"))
      (node (ref "U13") (pin "5") (pinfunction "VS_5") (pintype "passive"))
      (node (ref "U22") (pin "5") (pinfunction "VS_5") (pintype "passive"))
      (node (ref "U27") (pin "5") (pinfunction "V+_5") (pintype "power_in"))
    )
    (net (code "2") (name "+3V3") (class "Default")
      (node (ref "C111") (pin "2") (pinfunction "2_2") (pintype "passive"))
      (node (ref "C112") (pin "2") (pinfunction "2_2") (pintype "passive"))
      (node (ref "R27") (pin "2") (pinfunction "2_2") (pintype "passive"))
      (node (ref "U30") (pin "1") (pinfunction "VDD1_1") (pintype "passive"))
      (node (ref "U33") (pin "1") (pinfunction "VDD1_1") (pintype "passive"))
      (node (ref "VD6") (pin "2") (pinfunction "2_2") (pintype "passive"))
      (node (ref "VD7") (pin "2") (pinfunction "2_2") (pintype "passive"))
    )
    (net (code "3") (name "+5V") (class "Default")
      (node (ref "LED1") (pin "1") (pinfunction "1_1") (pintype "passive"))
      (node (ref "LED2") (pin "1") (pinfunction "1_1") (pintype "passive"))
      (node (ref "R18") (pin "1") (pinfunction "1_1") (pintype "passive"))
      (node (ref "R25") (pin "1") (pinfunction "1_1") (pintype "passive"))
      (node (ref "U29") (pin "2") (pinfunction "+Vin_2") (pintype "passive"))
      (node (ref "U31") (pin "2") (pinfunction "+Vin_2") (pintype "passive"))
    )
    (net (code "4") (name "/ACC4") (class "Default")
      (node (ref "Q2") (pin "1") (pinfunction "G_1") (pintype "passive"))
      (node (ref "Q3") (pin "1") (pinfunction "G_1") (pintype "passive"))
      (node (ref "R30") (pin "1") (pinfunction "1_1") (pintype "passive"))
      (node (ref "U14") (pin "10") (pinfunction "GATE_10") (pintype "passive"))
    )
    (net (code "5") (name "/ACC5") (class "Default")
      (node (ref "R28") (pin "1") (pinfunction "1_1") (pintype "passive"))
      (node (ref "R32") (pin "2") (pinfunction "2_2") (pintype "passive"))
      (node (ref "U14") (pin "2") (pinfunction "UV_2") (pintype "passive"))
    )
    (net (code "6") (name "/ACCUM_I") (class "Default")
      (node (ref "C90") (pin "2") (pinfunction "2_2") (pintype "passive"))
      (node (ref "R103") (pin "2") (pinfunction "2_2") (pintype "passive"))
    )
    (net (code "7") (name "/ACCUM_I+") (class "Default")
      (node (ref "R80") (pin "3") (pinfunction "1_3") (pintype "passive"))
      (node (ref "U22") (pin "2") (pinfunction "IN+_2") (pintype "passive"))
    )
    (net (code "8") (name "/ACCUM_I-") (class "Default")
      (node (ref "R80") (pin "4") (pinfunction "1_4") (pintype "passive"))
      (node (ref "U22") (pin "3") (pinfunction "IN-_3") (pintype "passive"))
    )
    (net (code "9") (name "/ACCUM_V") (class "Default")
      (node (ref "C101") (pin "1") (pinfunction "1_1") (pintype "passive"))
      (node (ref "R111") (pin "2") (pinfunction "2_2") (pintype "passive"))
      (node (ref "U27") (pin "1") (pinfunction "OUT_1") (pintype "passive"))
    )
    (net (code "10") (name "/ACC_I+") (class "Default")
      (node (ref "B2") (pin "2") (pinfunction "2_2") (pintype "passive"))
      (node (ref "U13") (pin "2") (pinfunction "IN+_2") (pintype "passive"))
    )
    (net (code "11") (name "/ACC_I-") (class "Default")
      (node (ref "B1") (pin "2") (pinfunction "2_2") (pintype "passive"))
      (node (ref "U13") (pin "3") (pinfunction "IN-_3") (pintype "passive"))
    )
    (net (code "12") (name "/ACC_PWR") (class "Default")
      (node (ref "C27") (pin "1") (pinfunction "1_1") (pintype "passive"))
      (node (ref "C28") (pin "1") (pinfunction "1_1") (pintype "passive"))
      (node (ref "Q2") (pin "3") (pinfunction "D_3") (pintype "passive"))
      (node (ref "R28") (pin "2") (pinfunction "2_2") (pintype "passive"))
      (node (ref "R29") (pin "2") (pinfunction "2_2") (pintype "passive"))
      (node (ref "R80") (pin "1") (pinfunction "1_1") (pintype "passive"))
      (node (ref "U14") (pin "1") (pinfunction "VIN_1") (pintype "passive"))
      (node (ref "VD3") (pin "2") (pinfunction "A_2") (pintype "passive"))
      (node (ref "X6") (pin "1") (pinfunction "1_1") (pintype "passive"))
    )
    (net (code "13") (name "/I1+5V") (class "Default")
      (node (ref "C105") (pin "1") (pinfunction "1_1") (pintype "passive"))
      (node (ref "U28") (pin "1") (pinfunction "IN_1") (pintype "power_in"))
      (node (ref "U28") (pin "3") (pinfunction "EN_3") (pintype "power_in"))
      (node (ref "U29") (pin "4") (pinfunction "+Vout_4") (pintype "passive"))
    )
    (net (code "14") (name "/I1_SPI1_CS") (class "Default")
      (node (ref "U17") (pin "9") (pinfunction "CS_9") (pintype "passive"))
      (node (ref "U30") (pin "12") (pinfunction "B3_12") (pintype "passive"))
    )
    (net (code "15") (name "/I1_SPI1_MISO") (class "Default")
      (node (ref "U17") (pin "12") (pinfunction "MISO_12") (pintype "passive"))
      (node (ref "U30") (pin "11") (pinfunction "B4_11") (pintype "passive"))
    )
    (net (code "16") (name "/I1_SPI1_MOSI") (class "Default")
      (node (ref "U17") (pin "10") (pinfunction "MOSI_10") (pintype "passive"))
      (node (ref "U30") (pin "13") (pinfunction "B2_13") (pintype "passive"))
    )
    (net (code "17") (name "/I1_SPI1_SCK") (class "Default")
      (node (ref "U17") (pin "11") (pinfunction "SCLK_11") (pintype "passive"))
      (node (ref "U30") (pin "14") (pinfunction "B1_14") (pintype "passive"))
    )
    (net (code "18") (name "/I2+5V") (class "Default")
      (node (ref "C108") (pin "1") (pinfunction "1_1") (pintype "passive"))
      (node (ref "U31") (pin "4") (pinfunction "+Vout_4") (pintype "passive"))
      (node (ref "U32") (pin "1") (pinfunction "IN_1") (pintype "power_in"))
      (node (ref "U32") (pin "3") (pinfunction "EN_3") (pintype "power_in"))
    )
    (net (code "19") (name "/I2_SPI1_CS") (class "Default")
      (node (ref "U15") (pin "9") (pinfunction "CS_9") (pintype "passive"))
      (node (ref "U33") (pin "12") (pinfunction "B3_12") (pintype "passive"))
    )
    (net (code "20") (name "/I2_SPI1_MISO") (class "Default")
      (node (ref "U15") (pin "12") (pinfunction "MISO_12") (pintype "passive"))
      (node (ref "U33") (pin "11") (pinfunction "B4_11") (pintype "passive"))
    )
    (net (code "21") (name "/I2_SPI1_MOSI") (class "Default")
      (node (ref "U15") (pin "10") (pinfunction "MOSI_10") (pintype "passive"))
      (node (ref "U33") (pin "13") (pinfunction "B2_13") (pintype "passive"))
    )
    (net (code "22") (name "/I2_SPI1_SCK") (class "Default")
      (node (ref "U15") (pin "11") (pinfunction "SCLK_11") (pintype "passive"))
      (node (ref "U33") (pin "14") (pinfunction "B1_14") (pintype "passive"))
    )
    (net (code "23") (name "/INVERT_I") (class "Default")
      (node (ref "C24") (pin "2") (pinfunction "2_2") (pintype "passive"))
      (node (ref "R21") (pin "2") (pinfunction "2_2") (pintype "passive"))
    )
    (net (code "24") (name "/INVERT_V") (class "Default")
      (node (ref "C25") (pin "2") (pinfunction "2_2") (pintype "passive"))
      (node (ref "R20") (pin "2") (pinfunction "2_2") (pintype "passive"))
      (node (ref "R23") (pin "1") (pinfunction "1_1") (pintype "passive"))
    )
    (net (code "25") (name "/INVSW_FAULT") (class "Default")
      (node (ref "R27") (pin "1") (pinfunction "1_1") (pintype "passive"))
      (node (ref "U14") (pin "7") (pinfunction "~{FAULT}_7") (pintype "passive"))
    )
    (net (code "26") (name "/INVSW_ON") (class "Default")
      (node (ref "R31") (pin "2") (pinfunction "2_2") (pintype "passive"))
      (node (ref "U14") (pin "6") (pinfunction "~{SHDN}_6") (pintype "passive"))
    )
    (net (code "27") (name "/INV_PATH_STATE") (class "Default")
      (node (ref "C49") (pin "1") (pinfunction "1_1") (pintype "passive"))
      (node (ref "R53") (pin "2") (pinfunction "2_2") (pintype "passive"))
      (node (ref "R54") (pin "2") (pinfunction "2_2") (pintype "passive"))
      (node (ref "VD7") (pin "3") (pinfunction "3_3") (pintype "passive"))
    )
    (net (code "28") (name "/INV_PWR") (class "Default")
      (node (ref "B2") (pin "1") (pinfunction "1_1") (pintype "passive"))
      (node (ref "R23") (pin "2") (pinfunction "2_2") (pintype "passive"))
      (node (ref "R24") (pin "1") (pinfunction "1_1") (pintype "passive"))
      (node (ref "U14") (pin "8") (pinfunction "VOUT_8") (pintype "passive"))
      (node (ref "X8") (pin "2") (pinfunction "2_2") (pintype "passive"))
    )
    (net (code "29") (name "/L1") (class "Default")
      (node (ref "R35_1") (pin "1") (pinfunction "1_1") (pintype "passive"))
      (node (ref "U15") (pin "1") (pinfunction "IP+_1") (pintype "passive"))
      (node (ref "U15") (pin "2") (pinfunction "IP+_2") (pintype "passive"))
      (node (ref "U15") (pin "3") (pinfunction "IP+_3") (pintype "passive"))
      (node (ref "U15") (pin "4") (pinfunction "IP+_4") (pintype "passive"))
      (node (ref "X10") (pin "1") (pinfunction "1_1") (pintype "passive"))
    )
    (net (code "30") (name "/L1.1") (class "Default")
      (node (ref "K2") (pin "8") (pinfunction "8_8") (pintype "passive"))
      (node (ref "U15") (pin "5") (pinfunction "IP-_5") (pintype "passive"))
      (node (ref "U15") (pin "6") (pinfunction "IP-_6") (pintype "passive"))
      (node (ref "U15") (pin "7") (pinfunction "IP-_7") (pintype "passive"))
      (node (ref "U15") (pin "8") (pinfunction "IP-_8") (pintype "passive"))
    )
    (net (code "31") (name "/L1_1") (class "Default")
      (node (ref "R35") (pin "1") (pinfunction "1_1") (pintype "passive"))
      (node (ref "R35_1") (pin "2") (pinfunction "2_2") (pintype "passive"))
    )
    (net (code "32") (name "/L1_2") (class "Default")
      (node (ref "R35") (pin "2") (pinfunction "2_2") (pintype "passive"))
      (node (ref "R36") (pin "1") (pinfunction "1_1") (pintype "passive"))
    )
    (net (code "33") (name "/L2") (class "Default")
      (node (ref "R48_1") (pin "1") (pinfunction "1_1") (pintype "passive"))
      (node (ref "U17") (pin "5") (pinfunction "IP-_5") (pintype "passive"))
      (node (ref "U17") (pin "6") (pinfunction "IP-_6") (pintype "passive"))
      (node (ref "U17") (pin "7") (pinfunction "IP-_7") (pintype "passive"))
      (node (ref "U17") (pin "8") (pinfunction "IP-_8") (pintype "passive"))
      (node (ref "X12") (pin "2") (pinfunction "2_2") (pintype "passive"))
    )
    (net (code "34") (name "/L2.1") (class "Default")
      (node (ref "K1") (pin "1") (pinfunction "1_1") (pintype "passive"))
      (node (ref "K2") (pin "1") (pinfunction "1_1") (pintype "passive"))
      (node (ref "U17") (pin "1") (pinfunction "IP+_1") (pintype "passive"))
      (node (ref "U17") (pin "2") (pinfunction "IP+_2") (pintype "passive"))
      (node (ref "U17") (pin "3") (pinfunction "IP+_3") (pintype "passive"))
      (node (ref "U17") (pin "4") (pinfunction "IP+_4") (pintype "passive"))
    )
    (net (code "35") (name "/L2_1") (class "Default")
      (node (ref "R48") (pin "2") (pinfunction "2_2") (pintype "passive"))
      (node (ref "R48_1") (pin "2") (pinfunction "2_2") (pintype "passive"))
    )
    (net (code "36") (name "/L2_2") (class "Default")
      (node (ref "R47") (pin "2") (pinfunction "2_2") (pintype "passive"))
      (node (ref "R48") (pin "1") (pinfunction "1_1") (pintype "passive"))
    )
    (net (code "37") (name "/L3") (class "Default")
      (node (ref "K1") (pin "8") (pinfunction "8_8") (pintype "passive"))
      (node (ref "X11") (pin "2") (pinfunction "2_2") (pintype "passive"))
    )
    (net (code "38") (name "/MAINS_PATH_STATE") (class "Default")
      (node (ref "C44") (pin "1") (pinfunction "1_1") (pintype "passive"))
      (node (ref "R51") (pin "2") (pinfunction "2_2") (pintype "passive"))
      (node (ref "R52") (pin "2") (pinfunction "2_2") (pintype "passive"))
      (node (ref "VD6") (pin "3") (pinfunction "3_3") (pintype "passive"))
    )
    (net (code "39") (name "/N1") (class "Default")
      (node (ref "K2") (pin "7") (pinfunction "7_7") (pintype "passive"))
      (node (ref "R40_1") (pin "1") (pinfunction "1_1") (pintype "passive"))
      (node (ref "X10") (pin "2") (pinfunction "2_2") (pintype "passive"))
    )
    (net (code "40") (name "/N1_1") (class "Default")
      (node (ref "R40") (pin "2") (pinfunction "2_2") (pintype "passive"))
      (node (ref "R40_1") (pin "2") (pinfunction "2_2") (pintype "passive"))
    )
    (net (code "41") (name "/N1_2") (class "Default")
      (node (ref "R39") (pin "2") (pinfunction "2_2") (pintype "passive"))
      (node (ref "R40") (pin "1") (pinfunction "1_1") (pintype "passive"))
    )
    (net (code "42") (name "/N1_3") (class "Default")
      (node (ref "R37") (pin "1") (pinfunction "1_1") (pintype "passive"))
      (node (ref "R39") (pin "1") (pinfunction "1_1") (pintype "passive"))
      (node (ref "U15") (pin "16") (pinfunction "VIMP_16") (pintype "passive"))
    )
    (net (code "43") (name "/N2") (class "Default")
      (node (ref "K1") (pin "2") (pinfunction "2_2") (pintype "passive"))
      (node (ref "K2") (pin "2") (pinfunction "2_2") (pintype "passive"))
      (node (ref "R44_1") (pin "1") (pinfunction "1_1") (pintype "passive"))
      (node (ref "X12") (pin "1") (pinfunction "1_1") (pintype "passive"))
    )
    (net (code "44") (name "/N2_1") (class "Default")
      (node (ref "R44") (pin "1") (pinfunction "1_1") (pintype "passive"))
      (node (ref "R44_1") (pin "2") (pinfunction "2_2") (pintype "passive"))
    )
    (net (code "45") (name "/N2_2") (class "Default")
      (node (ref "R44") (pin "2") (pinfunction "2_2") (pintype "passive"))
      (node (ref "R45") (pin "1") (pinfunction "1_1") (pintype "passive"))
    )
    (net (code "46") (name "/N2_3") (class "Default")
      (node (ref "R45") (pin "2") (pinfunction "2_2") (pintype "passive"))
      (node (ref "R46") (pin "2") (pinfunction "2_2") (pintype "passive"))
      (node (ref "U17") (pin "16") (pinfunction "VIMP_16") (pintype "passive"))
    )
    (net (code "47") (name "/N3") (class "Default")
      (node (ref "K1") (pin "7") (pinfunction "7_7") (pintype "passive"))
      (node (ref "X11") (pin "1") (pinfunction "1_1") (pintype "passive"))
    )
    (net (code "48") (name "/OUT1") (class "Default")
      (node (ref "Q1") (pin "1") (pinfunction "B_1") (pintype "passive"))
    )
    (net (code "49") (name "/OUT2") (class "Default")
      (node (ref "Q4") (pin "1") (pinfunction "B_1") (pintype "passive"))
    )
    (net (code "50") (name "/SPI0_CS") (class "Default")
      (node (ref "U33") (pin "5") (pinfunction "A3_5") (pintype "passive"))
    )
    (net (code "51") (name "/SPI0_MISO") (class "Default")
      (node (ref "U33") (pin "6") (pinfunction "A4_6") (pintype "passive"))
    )
    (net (code "52") (name "/SPI0_MOSI") (class "Default")
      (node (ref "U33") (pin "4") (pinfunction "A2_4") (pintype "passive"))
    )
    (net (code "53") (name "/SPI0_SCK") (class "Default")
      (node (ref "U33") (pin "3") (pinfunction "A1_3") (pintype "passive"))
    )
    (net (code "54") (name "/SPI1_CS") (class "Default")
      (node (ref "U30") (pin "5") (pinfunction "A3_5") (pintype "passive"))
    )
    (net (code "55") (name "/SPI1_MISO") (class "Default")
      (node (ref "U30") (pin "6") (pinfunction "A4_6") (pintype "passive"))
    )
    (net (code "56") (name "/SPI1_MOSI") (class "Default")
      (node (ref "U30") (pin "4") (pinfunction "A2_4") (pintype "passive"))
    )
    (net (code "57") (name "/SPI1_SCK") (class "Default")
      (node (ref "U30") (pin "3") (pinfunction "A1_3") (pintype "passive"))
    )
    (net (code "58") (name "/SW_INV_PATH") (class "Default")
      (node (ref "U16") (pin "1") (pinfunction "IN1_1") (pintype "power_in"))
    )
    (net (code "59") (name "/SW_MAINS_PATH") (class "Default")
      (node (ref "U16") (pin "2") (pinfunction "IN2_2") (pintype "power_in"))
    )
    (net (code "60") (name "ACC_DC_BUS") (class "Default")
      (node (ref "R110") (pin "1") (pinfunction "1_1") (pintype "passive"))
      (node (ref "R80") (pin "2") (pinfunction "2_2") (pintype "passive"))
    )
    (net (code "61") (name "AGND") (class "Default")
      (node (ref "C102") (pin "2") (pinfunction "2_2") (pintype "passive"))
      (node (ref "C103") (pin "2") (pinfunction "2_2") (pintype "passive"))
      (node (ref "C24") (pin "1") (pinfunction "1_1") (pintype "passive"))
      (node (ref "C25") (pin "1") (pinfunction "1_1") (pintype "passive"))
      (node (ref "C26") (pin "2") (pinfunction "2_2") (pintype "passive"))
      (node (ref "C77") (pin "2") (pinfunction "2_2") (pintype "passive"))
      (node (ref "C90") (pin "1") (pinfunction "1_1") (pintype "passive"))
      (node (ref "R112") (pin "1") (pinfunction "1_1") (pintype "passive"))
      (node (ref "R20") (pin "1") (pinfunction "1_1") (pintype "passive"))
      (node (ref "U13") (pin "4") (pinfunction "GND_4") (pintype "passive"))
      (node (ref "U22") (pin "4") (pinfunction "GND_4") (pintype "passive"))
      (node (ref "U27") (pin "2") (pinfunction "GND_2") (pintype "power_in"))
    )
    (net (code "62") (name "GND") (class "Default")
      (node (ref "C111") (pin "1") (pinfunction "1_1") (pintype "passive"))
      (node (ref "C112") (pin "1") (pinfunction "1_1") (pintype "passive"))
      (node (ref "C44") (pin "2") (pinfunction "2_2") (pintype "passive"))
      (node (ref "C49") (pin "2") (pinfunction "2_2") (pintype "passive"))
      (node (ref "Q1") (pin "2") (pinfunction "E_2") (pintype "passive"))
      (node (ref "Q4") (pin "2") (pinfunction "E_2") (pintype "passive"))
      (node (ref "R52") (pin "1") (pinfunction "1_1") (pintype "passive"))
      (node (ref "R54") (pin "1") (pinfunction "1_1") (pintype "passive"))
      (node (ref "U16") (pin "8") (pinfunction "GND_8") (pintype "power_in"))
      (node (ref "U29") (pin "1") (pinfunction "-Vin_1") (pintype "passive"))
      (node (ref "U30") (pin "2") (pinfunction "GND1_2") (pintype "passive"))
      (node (ref "U30") (pin "8") (pinfunction "GND1_8") (pintype "passive"))
      (node (ref "U31") (pin "1") (pinfunction "-Vin_1") (pintype "passive"))
      (node (ref "U33") (pin "2") (pinfunction "GND1_2") (pintype "passive"))
      (node (ref "U33") (pin "8") (pinfunction "GND1_8") (pintype "passive"))
      (node (ref "VD6") (pin "1") (pinfunction "1_1") (pintype "passive"))
      (node (ref "VD7") (pin "1") (pinfunction "1_1") (pintype "passive"))
    )
    (net (code "63") (name "I1+3V3") (class "Default")
      (node (ref "C106") (pin "1") (pinfunction "1_1") (pintype "passive"))
      (node (ref "C107") (pin "2") (pinfunction "2_2") (pintype "passive"))
      (node (ref "C50") (pin "1") (pinfunction "1_1") (pintype "passive"))
      (node (ref "U17") (pin "13") (pinfunction "VCC_13") (pintype "passive"))
      (node (ref "U28") (pin "5") (pinfunction "OUT_5") (pintype "power_in"))
      (node (ref "U30") (pin "16") (pinfunction "VDD2_16") (pintype "passive"))
    )
    (net (code "64") (name "I1_GND") (class "Default")
      (node (ref "C105") (pin "2") (pinfunction "2_2") (pintype "passive"))
      (node (ref "C106") (pin "2") (pinfunction "2_2") (pintype "passive"))
      (node (ref "C107") (pin "1") (pinfunction "1_1") (pintype "passive"))
      (node (ref "C50") (pin "2") (pinfunction "2_2") (pintype "passive"))
      (node (ref "R46") (pin "1") (pinfunction "1_1") (pintype "passive"))
      (node (ref "R47") (pin "1") (pinfunction "1_1") (pintype "passive"))
      (node (ref "U17") (pin "14") (pinfunction "GND_14") (pintype "passive"))
      (node (ref "U17") (pin "15") (pinfunction "VINN_15") (pintype "passive"))
      (node (ref "U28") (pin "2") (pinfunction "GND_2") (pintype "power_in"))
      (node (ref "U29") (pin "3") (pinfunction "-Vout_3") (pintype "passive"))
      (node (ref "U30") (pin "15") (pinfunction "GND2_15") (pintype "passive"))
      (node (ref "U30") (pin "9") (pinfunction "GND2_9") (pintype "passive"))
    )
    (net (code "65") (name "I2+3V3") (class "Default")
      (node (ref "C109") (pin "1") (pinfunction "1_1") (pintype "passive"))
      (node (ref "C110") (pin "2") (pinfunction "2_2") (pintype "passive"))
      (node (ref "C38") (pin "1") (pinfunction "1_1") (pintype "passive"))
      (node (ref "U15") (pin "13") (pinfunction "VCC_13") (pintype "passive"))
      (node (ref "U32") (pin "5") (pinfunction "OUT_5") (pintype "power_in"))
      (node (ref "U33") (pin "16") (pinfunction "VDD2_16") (pintype "passive"))
    )
    (net (code "66") (name "I2_GND") (class "Default")
      (node (ref "C108") (pin "2") (pinfunction "2_2") (pintype "passive"))
      (node (ref "C109") (pin "2") (pinfunction "2_2") (pintype "passive"))
      (node (ref "C110") (pin "1") (pinfunction "1_1") (pintype "passive"))
      (node (ref "C38") (pin "2") (pinfunction "2_2") (pintype "passive"))
      (node (ref "R36") (pin "2") (pinfunction "2_2") (pintype "passive"))
      (node (ref "R37") (pin "2") (pinfunction "2_2") (pintype "passive"))
      (node (ref "U15") (pin "14") (pinfunction "GND_14") (pintype "passive"))
      (node (ref "U15") (pin "15") (pinfunction "VINN_15") (pintype "passive"))
      (node (ref "U31") (pin "3") (pinfunction "-Vout_3") (pintype "passive"))
      (node (ref "U32") (pin "2") (pinfunction "GND_2") (pintype "power_in"))
      (node (ref "U33") (pin "15") (pinfunction "GND2_15") (pintype "passive"))
      (node (ref "U33") (pin "9") (pinfunction "GND2_9") (pintype "passive"))
    )
    (net (code "67") (name "Net-(C32-Pad1)") (class "Default")
      (node (ref "C32") (pin "1") (pinfunction "1_1") (pintype "passive"))
      (node (ref "R30") (pin "2") (pinfunction "2_2") (pintype "passive"))
    )
    (net (code "68") (name "Net-(LED1-Pad2)") (class "Default")
      (node (ref "LED1") (pin "2") (pinfunction "2_2") (pintype "passive"))
      (node (ref "R19") (pin "2") (pinfunction "2_2") (pintype "passive"))
    )
    (net (code "69") (name "Net-(LED2-Pad2)") (class "Default")
      (node (ref "LED2") (pin "2") (pinfunction "2_2") (pintype "passive"))
      (node (ref "R26") (pin "2") (pinfunction "2_2") (pintype "passive"))
    )
    (net (code "70") (name "Net-(OPT1-Pad1)") (class "Default")
      (node (ref "OPT1") (pin "1") (pinfunction "1_1") (pintype "passive"))
      (node (ref "R18") (pin "2") (pinfunction "2_2") (pintype "passive"))
    )
    (net (code "71") (name "Net-(OPT1-Pad4)") (class "Default")
      (node (ref "OPT1") (pin "4") (pinfunction "4_4") (pintype "passive"))
      (node (ref "X7") (pin "1") (pinfunction "1_1") (pintype "passive"))
    )
    (net (code "72") (name "Net-(OPT1-Pad6)") (class "Default")
      (node (ref "OPT1") (pin "6") (pinfunction "6_6") (pintype "passive"))
      (node (ref "X7") (pin "2") (pinfunction "2_2") (pintype "passive"))
    )
    (net (code "73") (name "Net-(OPT2-Pad1)") (class "Default")
      (node (ref "OPT2") (pin "1") (pinfunction "1_1") (pintype "passive"))
      (node (ref "R25") (pin "2") (pinfunction "2_2") (pintype "passive"))
    )
    (net (code "74") (name "Net-(OPT2-Pad4)") (class "Default")
      (node (ref "OPT2") (pin "4") (pinfunction "4_4") (pintype "passive"))
      (node (ref "X9") (pin "1") (pinfunction "1_1") (pintype "passive"))
    )
    (net (code "75") (name "Net-(OPT2-Pad6)") (class "Default")
      (node (ref "OPT2") (pin "6") (pinfunction "6_6") (pintype "passive"))
      (node (ref "X9") (pin "2") (pinfunction "2_2") (pintype "passive"))
    )
    (net (code "76") (name "Net-(Q1-C)") (class "Default")
      (node (ref "OPT1") (pin "2") (pinfunction "2_2") (pintype "passive"))
      (node (ref "Q1") (pin "3") (pinfunction "C_3") (pintype "passive"))
      (node (ref "R19") (pin "1") (pinfunction "1_1") (pintype "passive"))
    )
    (net (code "77") (name "Net-(Q2-S)") (class "Default")
      (node (ref "Q2") (pin "2") (pinfunction "S_2") (pintype "passive"))
      (node (ref "Q3") (pin "2") (pinfunction "S_2") (pintype "passive"))
    )
    (net (code "78") (name "Net-(Q3-D)") (class "Default")
      (node (ref "B1") (pin "1") (pinfunction "1_1") (pintype "passive"))
      (node (ref "Q3") (pin "3") (pinfunction "D_3") (pintype "passive"))
      (node (ref "R24") (pin "2") (pinfunction "2_2") (pintype "passive"))
      (node (ref "U14") (pin "9") (pinfunction "SENSE_9") (pintype "passive"))
    )
    (net (code "79") (name "Net-(Q4-C)") (class "Default")
      (node (ref "OPT2") (pin "2") (pinfunction "2_2") (pintype "passive"))
      (node (ref "Q4") (pin "3") (pinfunction "C_3") (pintype "passive"))
      (node (ref "R26") (pin "1") (pinfunction "1_1") (pintype "passive"))
    )
    (net (code "80") (name "Net-(U13-OUT)") (class "Default")
      (node (ref "R21") (pin "1") (pinfunction "1_1") (pintype "passive"))
      (node (ref "U13") (pin "8") (pinfunction "OUT_8") (pintype "passive"))
    )
    (net (code "81") (name "Net-(U14-OV)") (class "Default")
      (node (ref "R29") (pin "1") (pinfunction "1_1") (pintype "passive"))
      (node (ref "R33") (pin "2") (pinfunction "2_2") (pintype "passive"))
      (node (ref "U14") (pin "3") (pinfunction "OV_3") (pintype "passive"))
    )
    (net (code "82") (name "Net-(U14-RETRY)") (class "Default")
      (node (ref "C29") (pin "1") (pinfunction "1_1") (pintype "passive"))
      (node (ref "U14") (pin "4") (pinfunction "RETRY_4") (pintype "passive"))
    )
    (net (code "83") (name "Net-(U16-OUT1)") (class "Default")
      (node (ref "K1") (pin "3") (pinfunction "3_3") (pintype "passive"))
      (node (ref "U16") (pin "16") (pinfunction "OUT1_16") (pintype "power_in"))
    )
    (net (code "84") (name "Net-(U16-OUT2)") (class "Default")
      (node (ref "K2") (pin "3") (pinfunction "3_3") (pintype "passive"))
      (node (ref "U16") (pin "15") (pinfunction "OUT2_15") (pintype "power_in"))
    )
    (net (code "85") (name "Net-(U22-OUT)") (class "Default")
      (node (ref "R103") (pin "1") (pinfunction "1_1") (pintype "passive"))
      (node (ref "U22") (pin "8") (pinfunction "OUT_8") (pintype "passive"))
    )
    (net (code "86") (name "Net-(U27-IN+)") (class "Default")
      (node (ref "C102") (pin "1") (pinfunction "1_1") (pintype "passive"))
      (node (ref "R110") (pin "2") (pinfunction "2_2") (pintype "passive"))
      (node (ref "R112") (pin "2") (pinfunction "2_2") (pintype "passive"))
      (node (ref "U27") (pin "3") (pinfunction "IN+_3") (pintype "passive"))
    )
    (net (code "87") (name "Net-(U27-IN-)") (class "Default")
      (node (ref "C101") (pin "2") (pinfunction "2_2") (pintype "passive"))
      (node (ref "R109") (pin "2") (pinfunction "2_2") (pintype "passive"))
      (node (ref "R111") (pin "1") (pinfunction "1_1") (pintype "passive"))
      (node (ref "U27") (pin "4") (pinfunction "IN-_4") (pintype "passive"))
    )
    (net (code "88") (name "Net-(VD4-C)") (class "Default")
      (node (ref "K1") (pin "5") (pinfunction "5_5") (pintype "passive"))
      (node (ref "K2") (pin "6") (pinfunction "6_6") (pintype "passive"))
      (node (ref "R51") (pin "1") (pinfunction "1_1") (pintype "passive"))
      (node (ref "VD4") (pin "1") (pinfunction "C_1") (pintype "passive"))
    )
    (net (code "89") (name "Net-(VD5-C)") (class "Default")
      (node (ref "K1") (pin "6") (pinfunction "6_6") (pintype "passive"))
      (node (ref "K2") (pin "5") (pinfunction "5_5") (pintype "passive"))
      (node (ref "R53") (pin "1") (pinfunction "1_1") (pintype "passive"))
      (node (ref "VD5") (pin "1") (pinfunction "C_1") (pintype "passive"))
    )
    (net (code "90") (name "PGND") (class "Default")
      (node (ref "C27") (pin "2") (pinfunction "2_2") (pintype "passive"))
      (node (ref "C28") (pin "2") (pinfunction "2_2") (pintype "passive"))
      (node (ref "C29") (pin "2") (pinfunction "2_2") (pintype "passive"))
      (node (ref "C32") (pin "2") (pinfunction "2_2") (pintype "passive"))
      (node (ref "R109") (pin "1") (pinfunction "1_1") (pintype "passive"))
      (node (ref "R31") (pin "1") (pinfunction "1_1") (pintype "passive"))
      (node (ref "R32") (pin "1") (pinfunction "1_1") (pintype "passive"))
      (node (ref "R33") (pin "1") (pinfunction "1_1") (pintype "passive"))
      (node (ref "U14") (pin "5") (pinfunction "GND_5") (pintype "passive"))
      (node (ref "VD3") (pin "1") (pinfunction "C_1") (pintype "passive"))
      (node (ref "X6") (pin "2") (pinfunction "2_2") (pintype "passive"))
      (node (ref "X8") (pin "1") (pinfunction "1_1") (pintype "passive"))
    )
    (net (code "91") (name "PWR24F") (class "Default")
      (node (ref "K1") (pin "4") (pinfunction "4_4") (pintype "passive"))
      (node (ref "K2") (pin "4") (pinfunction "4_4") (pintype "passive"))
      (node (ref "U16") (pin "9") (pinfunction "COMD_9") (pintype "power_in"))
      (node (ref "VD4") (pin "2") (pinfunction "A_2") (pintype "passive"))
      (node (ref "VD5") (pin "2") (pinfunction "A_2") (pintype "passive"))
    )
    (net (code "92") (name "VREF_1.65V") (class "Default")
      (node (ref "U13") (pin "6") (pinfunction "REF2_6") (pintype "passive"))
      (node (ref "U13") (pin "7") (pinfunction "REF1_7") (pintype "passive"))
      (node (ref "U22") (pin "6") (pinfunction "REF2_6") (pintype "passive"))
      (node (ref "U22") (pin "7") (pinfunction "REF1_7") (pintype "passive"))
    )
    (net (code "93") (name "unconnected-(OPT1-Pad5)") (class "Default")
      (node (ref "OPT1") (pin "5") (pinfunction "5_5") (pintype "passive"))
    )
    (net (code "94") (name "unconnected-(OPT2-Pad5)") (class "Default")
      (node (ref "OPT2") (pin "5") (pinfunction "5_5") (pintype "passive"))
    )
    (net (code "95") (name "unconnected-(U13-NC-Pad1)") (class "Default")
      (node (ref "U13") (pin "1") (pinfunction "NC_1") (pintype "passive"))
    )
    (net (code "96") (name "unconnected-(U16-IN3-Pad3)") (class "Default")
      (node (ref "U16") (pin "3") (pinfunction "IN3_3") (pintype "power_in"))
    )
    (net (code "97") (name "unconnected-(U16-IN4-Pad4)") (class "Default")
      (node (ref "U16") (pin "4") (pinfunction "IN4_4") (pintype "power_in"))
    )
    (net (code "98") (name "unconnected-(U16-IN5-Pad5)") (class "Default")
      (node (ref "U16") (pin "5") (pinfunction "IN5_5") (pintype "power_in"))
    )
    (net (code "99") (name "unconnected-(U16-IN6-Pad6)") (class "Default")
      (node (ref "U16") (pin "6") (pinfunction "IN6_6") (pintype "power_in"))
    )
    (net (code "100") (name "unconnected-(U16-IN7-Pad7)") (class "Default")
      (node (ref "U16") (pin "7") (pinfunction "IN7_7") (pintype "power_in"))
    )
    (net (code "101") (name "unconnected-(U16-OUT3-Pad14)") (class "Default")
      (node (ref "U16") (pin "14") (pinfunction "OUT3_14") (pintype "power_in"))
    )
    (net (code "102") (name "unconnected-(U16-OUT4-Pad13)") (class "Default")
      (node (ref "U16") (pin "13") (pinfunction "OUT4_13") (pintype "power_in"))
    )
    (net (code "103") (name "unconnected-(U16-OUT5-Pad12)") (class "Default")
      (node (ref "U16") (pin "12") (pinfunction "OUT5_12") (pintype "power_in"))
    )
    (net (code "104") (name "unconnected-(U16-OUT6-Pad11)") (class "Default")
      (node (ref "U16") (pin "11") (pinfunction "OUT6_11") (pintype "power_in"))
    )
    (net (code "105") (name "unconnected-(U16-OUT7-Pad10)") (class "Default")
      (node (ref "U16") (pin "10") (pinfunction "OUT7_10") (pintype "power_in"))
    )
    (net (code "106") (name "unconnected-(U22-NC-Pad1)") (class "Default")
      (node (ref "U22") (pin "1") (pinfunction "NC_1") (pintype "passive"))
    )
    (net (code "107") (name "unconnected-(U30-EN2-Pad10)") (class "Default")
      (node (ref "U30") (pin "10") (pinfunction "EN2_10") (pintype "passive"))
    )
    (net (code "108") (name "unconnected-(U30-NC-Pad7)") (class "Default")
      (node (ref "U30") (pin "7") (pinfunction "NC_7") (pintype "passive"))
    )
    (net (code "109") (name "unconnected-(U33-EN2-Pad10)") (class "Default")
      (node (ref "U33") (pin "10") (pinfunction "EN2_10") (pintype "passive"))
    )
    (net (code "110") (name "unconnected-(U33-NC-Pad7)") (class "Default")
      (node (ref "U33") (pin "7") (pinfunction "NC_7") (pintype "passive"))
    )
  )
)
